# keyboard_controller.net
KiCad netlist of a schematic drawn in Altium Designer
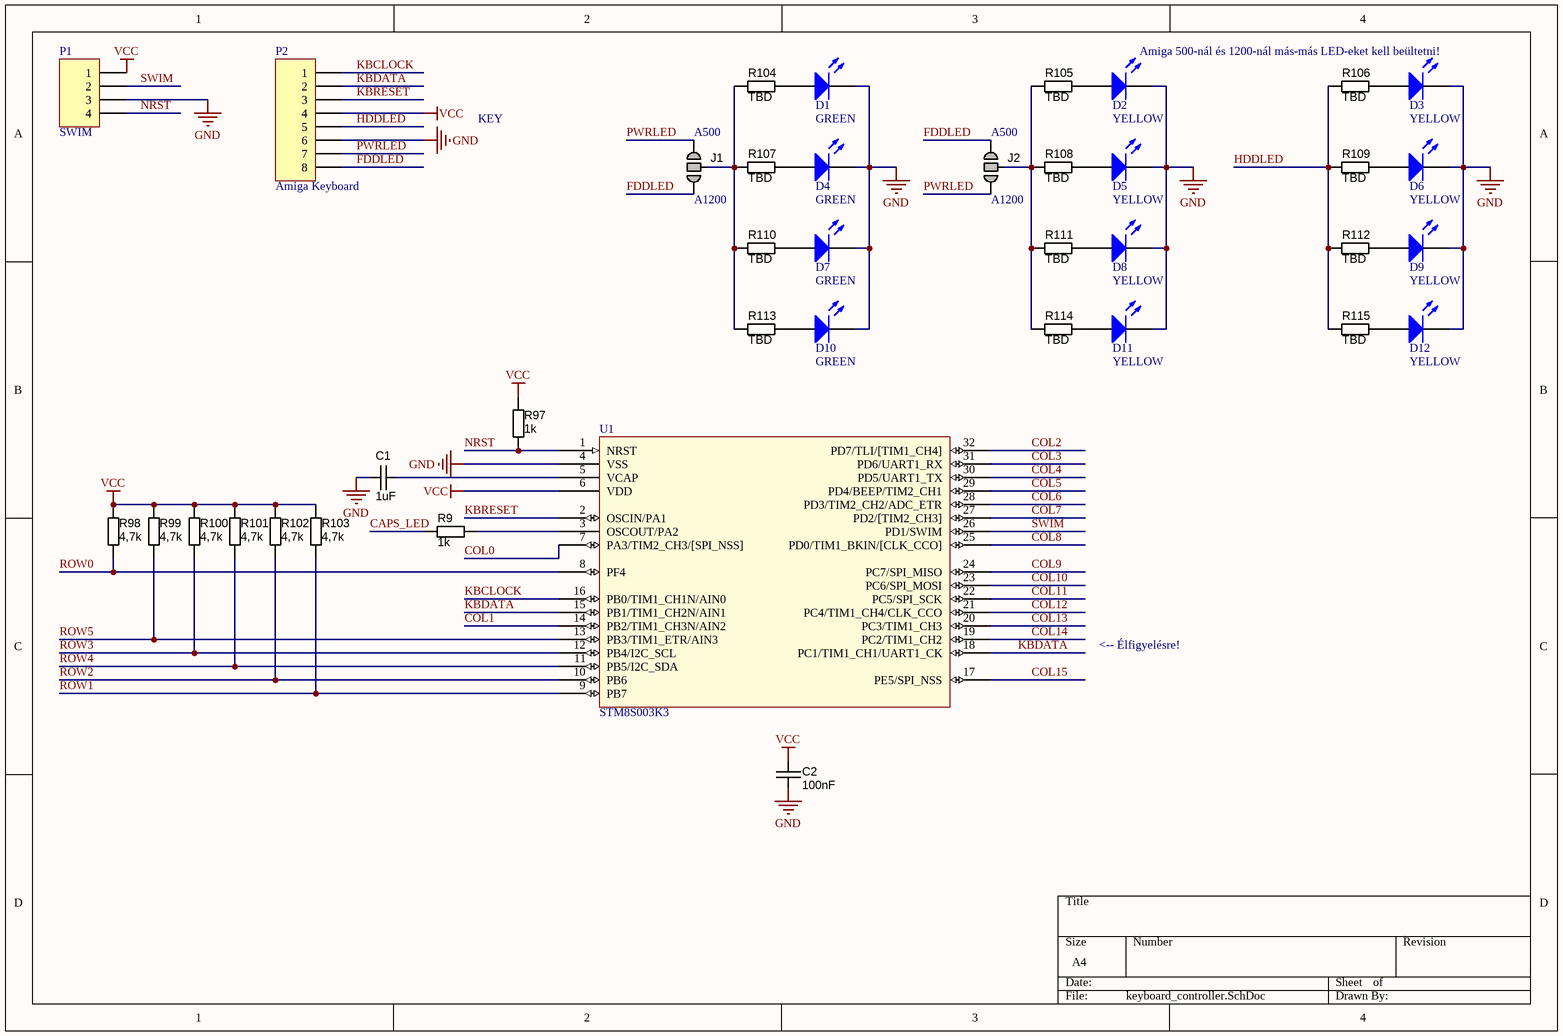
[diagram p0: keyboard_controller.SchDoc]

(export (version "E")
  (design (tool "Eeschema 10.0.6"))
  (components
    (comp (ref "C1")
      (value "1uF")
      (footprint "CAPC2012X135N")
      (description "Capacitor SMD Cer X7R 0805")
      (fields (field (name "TOLERANCE") "±10%") (field (name "Comment") "0805"))
      (libsource (lib "PBL - Capacitors") (part "CAPC_1u_0805_X7R_16V_10%"))
    )
    (comp (ref "C2")
      (value "100nF")
      (footprint "CAPC2012X135N")
      (description "Capacitor SMD Cer X7R 0805")
      (fields (field (name "TOLERANCE") "±10%") (field (name "Comment") "0805"))
      (libsource (lib "PBL - Capacitors") (part "CAPC_1u_0805_X7R_16V_10%"))
    )
    (comp (ref "D1")
      (value "GREEN")
      (footprint "LEDSQ_5mm")
      (description "Typical LED")
      (fields (field (name "PUBLISHER") "Altium Limited"))
      (libsource (lib "keyboard_library") (part "LED"))
    )
    (comp (ref "D2")
      (value "YELLOW")
      (footprint "LEDSQ_5mm")
      (description "Typical LED")
      (fields (field (name "PUBLISHER") "Altium Limited"))
      (libsource (lib "keyboard_library") (part "LED"))
    )
    (comp (ref "D3")
      (value "YELLOW")
      (footprint "LEDSQ_5mm")
      (description "Typical LED")
      (fields (field (name "PUBLISHER") "Altium Limited"))
      (libsource (lib "keyboard_library") (part "LED"))
    )
    (comp (ref "D4")
      (value "GREEN")
      (footprint "LEDSQ_5mm")
      (description "Typical LED")
      (fields (field (name "PUBLISHER") "Altium Limited"))
      (libsource (lib "keyboard_library") (part "LED"))
    )
    (comp (ref "D5")
      (value "YELLOW")
      (footprint "LEDSQ_5mm")
      (description "Typical LED")
      (fields (field (name "PUBLISHER") "Altium Limited"))
      (libsource (lib "keyboard_library") (part "LED"))
    )
    (comp (ref "D6")
      (value "YELLOW")
      (footprint "LEDSQ_5mm")
      (description "Typical LED")
      (fields (field (name "PUBLISHER") "Altium Limited"))
      (libsource (lib "keyboard_library") (part "LED"))
    )
    (comp (ref "D7")
      (value "GREEN")
      (footprint "LEDSQ_5mm")
      (description "Typical LED")
      (fields (field (name "PUBLISHER") "Altium Limited"))
      (libsource (lib "keyboard_library") (part "LED"))
    )
    (comp (ref "D8")
      (value "YELLOW")
      (footprint "LEDSQ_5mm")
      (description "Typical LED")
      (fields (field (name "PUBLISHER") "Altium Limited"))
      (libsource (lib "keyboard_library") (part "LED"))
    )
    (comp (ref "D9")
      (value "YELLOW")
      (footprint "LEDSQ_5mm")
      (description "Typical LED")
      (fields (field (name "PUBLISHER") "Altium Limited"))
      (libsource (lib "keyboard_library") (part "LED"))
    )
    (comp (ref "D10")
      (value "GREEN")
      (footprint "LEDSQ_5mm")
      (description "Typical LED")
      (fields (field (name "PUBLISHER") "Altium Limited"))
      (libsource (lib "keyboard_library") (part "LED"))
    )
    (comp (ref "D11")
      (value "YELLOW")
      (footprint "LEDSQ_5mm")
      (description "Typical LED")
      (fields (field (name "PUBLISHER") "Altium Limited"))
      (libsource (lib "keyboard_library") (part "LED"))
    )
    (comp (ref "D12")
      (value "YELLOW")
      (footprint "LEDSQ_5mm")
      (description "Typical LED")
      (fields (field (name "PUBLISHER") "Altium Limited"))
      (libsource (lib "keyboard_library") (part "LED"))
    )
    (comp (ref "J1")
      (value "Jumper")
      (footprint "Jump_3Way")
      (description "SMD jumper")
      (libsource (lib "PBL - Pads and Jumpers") (part "JUMP_3WAY"))
    )
    (comp (ref "J2")
      (value "Jumper")
      (footprint "Jump_3Way")
      (description "SMD jumper")
      (libsource (lib "PBL - Pads and Jumpers") (part "JUMP_3WAY"))
    )
    (comp (ref "P1")
      (value "SWIM")
      (footprint "HDR1X4")
      (description "Header, 4-Pin")
      (fields (field (name "PUBLISHER") "Altium Limited"))
      (libsource (lib "Miscellaneous Connectors") (part "Header 4"))
    )
    (comp (ref "P2")
      (value "Amiga Keyboard")
      (footprint "HDR1X8")
      (description "Header, 8-Pin")
      (fields (field (name "PUBLISHER") "Altium Limited"))
      (libsource (lib "Miscellaneous Connectors") (part "Header 8"))
    )
    (comp (ref "R9")
      (value "1k")
      (footprint "RESC2012N_ZERO")
      (description "Resistor SMD chip 0.0 Ohm 0.125W 0805")
      (fields (field (name "Comment") "0805"))
      (libsource (lib "") (part "RES_0R_0805_1"))
    )
    (comp (ref "R97")
      (value "1k")
      (footprint "RESC2012N_ZERO")
      (description "Resistor SMD chip 0.0 Ohm 0.125W 0805")
      (fields (field (name "Comment") "0805"))
      (libsource (lib "ZX_Spectrum_library") (part "RES_0R_0805"))
    )
    (comp (ref "R98")
      (value "4,7k")
      (footprint "RESC2012N_ZERO")
      (description "Resistor SMD chip 0.0 Ohm 0.125W 0805")
      (fields (field (name "Comment") "0805"))
      (libsource (lib "ZX_Spectrum_library") (part "RES_0R_0805"))
    )
    (comp (ref "R99")
      (value "4,7k")
      (footprint "RESC2012N_ZERO")
      (description "Resistor SMD chip 0.0 Ohm 0.125W 0805")
      (fields (field (name "Comment") "0805"))
      (libsource (lib "ZX_Spectrum_library") (part "RES_0R_0805"))
    )
    (comp (ref "R100")
      (value "4,7k")
      (footprint "RESC2012N_ZERO")
      (description "Resistor SMD chip 0.0 Ohm 0.125W 0805")
      (fields (field (name "Comment") "0805"))
      (libsource (lib "ZX_Spectrum_library") (part "RES_0R_0805"))
    )
    (comp (ref "R101")
      (value "4,7k")
      (footprint "RESC2012N_ZERO")
      (description "Resistor SMD chip 0.0 Ohm 0.125W 0805")
      (fields (field (name "Comment") "0805"))
      (libsource (lib "ZX_Spectrum_library") (part "RES_0R_0805"))
    )
    (comp (ref "R102")
      (value "4,7k")
      (footprint "RESC2012N_ZERO")
      (description "Resistor SMD chip 0.0 Ohm 0.125W 0805")
      (fields (field (name "Comment") "0805"))
      (libsource (lib "ZX_Spectrum_library") (part "RES_0R_0805"))
    )
    (comp (ref "R103")
      (value "4,7k")
      (footprint "RESC2012N_ZERO")
      (description "Resistor SMD chip 0.0 Ohm 0.125W 0805")
      (fields (field (name "Comment") "0805"))
      (libsource (lib "ZX_Spectrum_library") (part "RES_0R_0805"))
    )
    (comp (ref "R104")
      (value "TBD")
      (footprint "RESC2012N_ZERO")
      (description "Resistor SMD chip 0.0 Ohm 0.125W 0805")
      (fields (field (name "Comment") "0805"))
      (libsource (lib "") (part "RES_0R_0805_1"))
    )
    (comp (ref "R105")
      (value "TBD")
      (footprint "RESC2012N_ZERO")
      (description "Resistor SMD chip 0.0 Ohm 0.125W 0805")
      (fields (field (name "Comment") "0805"))
      (libsource (lib "") (part "RES_0R_0805_1"))
    )
    (comp (ref "R106")
      (value "TBD")
      (footprint "RESC2012N_ZERO")
      (description "Resistor SMD chip 0.0 Ohm 0.125W 0805")
      (fields (field (name "Comment") "0805"))
      (libsource (lib "") (part "RES_0R_0805_1"))
    )
    (comp (ref "R107")
      (value "TBD")
      (footprint "RESC2012N_ZERO")
      (description "Resistor SMD chip 0.0 Ohm 0.125W 0805")
      (fields (field (name "Comment") "0805"))
      (libsource (lib "") (part "RES_0R_0805_1"))
    )
    (comp (ref "R108")
      (value "TBD")
      (footprint "RESC2012N_ZERO")
      (description "Resistor SMD chip 0.0 Ohm 0.125W 0805")
      (fields (field (name "Comment") "0805"))
      (libsource (lib "") (part "RES_0R_0805_1"))
    )
    (comp (ref "R109")
      (value "TBD")
      (footprint "RESC2012N_ZERO")
      (description "Resistor SMD chip 0.0 Ohm 0.125W 0805")
      (fields (field (name "Comment") "0805"))
      (libsource (lib "") (part "RES_0R_0805_1"))
    )
    (comp (ref "R110")
      (value "TBD")
      (footprint "RESC2012N_ZERO")
      (description "Resistor SMD chip 0.0 Ohm 0.125W 0805")
      (fields (field (name "Comment") "0805"))
      (libsource (lib "") (part "RES_0R_0805_1"))
    )
    (comp (ref "R111")
      (value "TBD")
      (footprint "RESC2012N_ZERO")
      (description "Resistor SMD chip 0.0 Ohm 0.125W 0805")
      (fields (field (name "Comment") "0805"))
      (libsource (lib "") (part "RES_0R_0805_1"))
    )
    (comp (ref "R112")
      (value "TBD")
      (footprint "RESC2012N_ZERO")
      (description "Resistor SMD chip 0.0 Ohm 0.125W 0805")
      (fields (field (name "Comment") "0805"))
      (libsource (lib "") (part "RES_0R_0805_1"))
    )
    (comp (ref "R113")
      (value "TBD")
      (footprint "RESC2012N_ZERO")
      (description "Resistor SMD chip 0.0 Ohm 0.125W 0805")
      (fields (field (name "Comment") "0805"))
      (libsource (lib "") (part "RES_0R_0805_1"))
    )
    (comp (ref "R114")
      (value "TBD")
      (footprint "RESC2012N_ZERO")
      (description "Resistor SMD chip 0.0 Ohm 0.125W 0805")
      (fields (field (name "Comment") "0805"))
      (libsource (lib "") (part "RES_0R_0805_1"))
    )
    (comp (ref "R115")
      (value "TBD")
      (footprint "RESC2012N_ZERO")
      (description "Resistor SMD chip 0.0 Ohm 0.125W 0805")
      (fields (field (name "Comment") "0805"))
      (libsource (lib "") (part "RES_0R_0805_1"))
    )
    (comp (ref "U1")
      (value "STM8S003K3")
      (footprint "LQFP32_M")
      (description "ST Microelectronics STM8S003K3 microcontroller")
      (libsource (lib "keyboard_library") (part "STM8S003K3"))
    )
  )
  (nets
    (net (code "1") (name "/CAPS_LED") (class "Default")
      (node (ref "R9") (pin "1") (pinfunction "1_1") (pintype "passive"))
    )
    (net (code "2") (name "/COL0") (class "Default")
      (node (ref "U1") (pin "7") (pinfunction "PA3/TIM2_CH3/[SPI_NSS]_7") (pintype "bidirectional"))
    )
    (net (code "3") (name "/COL1") (class "Default")
      (node (ref "U1") (pin "14") (pinfunction "PB2/TIM1_CH3N/AIN2_14") (pintype "bidirectional"))
    )
    (net (code "4") (name "/COL2") (class "Default")
      (node (ref "U1") (pin "32") (pinfunction "PD7/TLI/[TIM1_CH4]_32") (pintype "bidirectional"))
    )
    (net (code "5") (name "/COL3") (class "Default")
      (node (ref "U1") (pin "31") (pinfunction "PD6/UART1_RX_31") (pintype "bidirectional"))
    )
    (net (code "6") (name "/COL4") (class "Default")
      (node (ref "U1") (pin "30") (pinfunction "PD5/UART1_TX_30") (pintype "bidirectional"))
    )
    (net (code "7") (name "/COL5") (class "Default")
      (node (ref "U1") (pin "29") (pinfunction "PD4/BEEP/TIM2_CH1_29") (pintype "bidirectional"))
    )
    (net (code "8") (name "/COL6") (class "Default")
      (node (ref "U1") (pin "28") (pinfunction "PD3/TIM2_CH2/ADC_ETR_28") (pintype "bidirectional"))
    )
    (net (code "9") (name "/COL7") (class "Default")
      (node (ref "U1") (pin "27") (pinfunction "PD2/[TIM2_CH3]_27") (pintype "bidirectional"))
    )
    (net (code "10") (name "/COL8") (class "Default")
      (node (ref "U1") (pin "25") (pinfunction "PD0/TIM1_BKIN/[CLK_CCO]_25") (pintype "bidirectional"))
    )
    (net (code "11") (name "/COL9") (class "Default")
      (node (ref "U1") (pin "24") (pinfunction "PC7/SPI_MISO_24") (pintype "bidirectional"))
    )
    (net (code "12") (name "/COL10") (class "Default")
      (node (ref "U1") (pin "23") (pinfunction "PC6/SPI_MOSI_23") (pintype "bidirectional"))
    )
    (net (code "13") (name "/COL11") (class "Default")
      (node (ref "U1") (pin "22") (pinfunction "PC5/SPI_SCK_22") (pintype "bidirectional"))
    )
    (net (code "14") (name "/COL12") (class "Default")
      (node (ref "U1") (pin "21") (pinfunction "PC4/TIM1_CH4/CLK_CCO_21") (pintype "bidirectional"))
    )
    (net (code "15") (name "/COL13") (class "Default")
      (node (ref "U1") (pin "20") (pinfunction "PC3/TIM1_CH3_20") (pintype "bidirectional"))
    )
    (net (code "16") (name "/COL14") (class "Default")
      (node (ref "U1") (pin "19") (pinfunction "PC2/TIM1_CH2_19") (pintype "bidirectional"))
    )
    (net (code "17") (name "/COL15") (class "Default")
      (node (ref "U1") (pin "17") (pinfunction "PE5/SPI_NSS_17") (pintype "bidirectional"))
    )
    (net (code "18") (name "/FDDLED") (class "Default")
      (node (ref "J1") (pin "1") (pinfunction "1_1") (pintype "passive"))
      (node (ref "J2") (pin "3") (pinfunction "3_3") (pintype "passive"))
      (node (ref "P2") (pin "8") (pinfunction "8_8") (pintype "passive"))
    )
    (net (code "19") (name "/HDDLED") (class "Default")
      (node (ref "P2") (pin "5") (pinfunction "5_5") (pintype "passive"))
      (node (ref "R106") (pin "1") (pinfunction "1_1") (pintype "passive"))
      (node (ref "R109") (pin "1") (pinfunction "1_1") (pintype "passive"))
      (node (ref "R112") (pin "1") (pinfunction "1_1") (pintype "passive"))
      (node (ref "R115") (pin "1") (pinfunction "1_1") (pintype "passive"))
    )
    (net (code "20") (name "/KBCLOCK") (class "Default")
      (node (ref "P2") (pin "1") (pinfunction "1_1") (pintype "passive"))
      (node (ref "U1") (pin "16") (pinfunction "PB0/TIM1_CH1N/AIN0_16") (pintype "bidirectional"))
    )
    (net (code "21") (name "/KBDATA") (class "Default")
      (node (ref "P2") (pin "2") (pinfunction "2_2") (pintype "passive"))
      (node (ref "U1") (pin "15") (pinfunction "PB1/TIM1_CH2N/AIN1_15") (pintype "bidirectional"))
      (node (ref "U1") (pin "18") (pinfunction "PC1/TIM1_CH1/UART1_CK_18") (pintype "bidirectional"))
    )
    (net (code "22") (name "/KBRESET") (class "Default")
      (node (ref "P2") (pin "3") (pinfunction "3_3") (pintype "passive"))
      (node (ref "U1") (pin "2") (pinfunction "OSCIN/PA1_2") (pintype "bidirectional"))
    )
    (net (code "23") (name "/NRST") (class "Default")
      (node (ref "P1") (pin "4") (pinfunction "4_4") (pintype "passive"))
      (node (ref "R97") (pin "1") (pinfunction "1_1") (pintype "passive"))
      (node (ref "U1") (pin "1") (pinfunction "NRST_1") (pintype "input"))
    )
    (net (code "24") (name "/PWRLED") (class "Default")
      (node (ref "J1") (pin "3") (pinfunction "3_3") (pintype "passive"))
      (node (ref "J2") (pin "1") (pinfunction "1_1") (pintype "passive"))
      (node (ref "P2") (pin "7") (pinfunction "7_7") (pintype "passive"))
    )
    (net (code "25") (name "/ROW0") (class "Default")
      (node (ref "R98") (pin "1") (pinfunction "1_1") (pintype "passive"))
      (node (ref "U1") (pin "8") (pinfunction "PF4_8") (pintype "bidirectional"))
    )
    (net (code "26") (name "/ROW1") (class "Default")
      (node (ref "R103") (pin "1") (pinfunction "1_1") (pintype "passive"))
      (node (ref "U1") (pin "9") (pinfunction "PB7_9") (pintype "bidirectional"))
    )
    (net (code "27") (name "/ROW2") (class "Default")
      (node (ref "R102") (pin "1") (pinfunction "1_1") (pintype "passive"))
      (node (ref "U1") (pin "10") (pinfunction "PB6_10") (pintype "bidirectional"))
    )
    (net (code "28") (name "/ROW3") (class "Default")
      (node (ref "R100") (pin "1") (pinfunction "1_1") (pintype "passive"))
      (node (ref "U1") (pin "12") (pinfunction "PB4/I2C_SCL_12") (pintype "bidirectional"))
    )
    (net (code "29") (name "/ROW4") (class "Default")
      (node (ref "R101") (pin "1") (pinfunction "1_1") (pintype "passive"))
      (node (ref "U1") (pin "11") (pinfunction "PB5/I2C_SDA_11") (pintype "bidirectional"))
    )
    (net (code "30") (name "/ROW5") (class "Default")
      (node (ref "R99") (pin "1") (pinfunction "1_1") (pintype "passive"))
      (node (ref "U1") (pin "13") (pinfunction "PB3/TIM1_ETR/AIN3_13") (pintype "bidirectional"))
    )
    (net (code "31") (name "/SWIM") (class "Default")
      (node (ref "P1") (pin "2") (pinfunction "2_2") (pintype "passive"))
      (node (ref "U1") (pin "26") (pinfunction "PD1/SWIM_26") (pintype "bidirectional"))
    )
    (net (code "32") (name "GND") (class "Default")
      (node (ref "C1") (pin "2") (pintype "passive"))
      (node (ref "C2") (pin "2") (pintype "passive"))
      (node (ref "D1") (pin "2") (pinfunction "K_2") (pintype "passive"))
      (node (ref "D10") (pin "2") (pinfunction "K_2") (pintype "passive"))
      (node (ref "D11") (pin "2") (pinfunction "K_2") (pintype "passive"))
      (node (ref "D12") (pin "2") (pinfunction "K_2") (pintype "passive"))
      (node (ref "D2") (pin "2") (pinfunction "K_2") (pintype "passive"))
      (node (ref "D3") (pin "2") (pinfunction "K_2") (pintype "passive"))
      (node (ref "D4") (pin "2") (pinfunction "K_2") (pintype "passive"))
      (node (ref "D5") (pin "2") (pinfunction "K_2") (pintype "passive"))
      (node (ref "D6") (pin "2") (pinfunction "K_2") (pintype "passive"))
      (node (ref "D7") (pin "2") (pinfunction "K_2") (pintype "passive"))
      (node (ref "D8") (pin "2") (pinfunction "K_2") (pintype "passive"))
      (node (ref "D9") (pin "2") (pinfunction "K_2") (pintype "passive"))
      (node (ref "P1") (pin "3") (pinfunction "3_3") (pintype "passive"))
      (node (ref "P2") (pin "6") (pinfunction "6_6") (pintype "passive"))
      (node (ref "U1") (pin "4") (pinfunction "VSS_4") (pintype "power_in"))
    )
    (net (code "33") (name "Net-(D1-A)") (class "Default")
      (node (ref "D1") (pin "1") (pinfunction "A_1") (pintype "passive"))
      (node (ref "R104") (pin "2") (pinfunction "2_2") (pintype "passive"))
    )
    (net (code "34") (name "Net-(D2-A)") (class "Default")
      (node (ref "D2") (pin "1") (pinfunction "A_1") (pintype "passive"))
      (node (ref "R105") (pin "2") (pinfunction "2_2") (pintype "passive"))
    )
    (net (code "35") (name "Net-(D3-A)") (class "Default")
      (node (ref "D3") (pin "1") (pinfunction "A_1") (pintype "passive"))
      (node (ref "R106") (pin "2") (pinfunction "2_2") (pintype "passive"))
    )
    (net (code "36") (name "Net-(D4-A)") (class "Default")
      (node (ref "D4") (pin "1") (pinfunction "A_1") (pintype "passive"))
      (node (ref "R107") (pin "2") (pinfunction "2_2") (pintype "passive"))
    )
    (net (code "37") (name "Net-(D5-A)") (class "Default")
      (node (ref "D5") (pin "1") (pinfunction "A_1") (pintype "passive"))
      (node (ref "R108") (pin "2") (pinfunction "2_2") (pintype "passive"))
    )
    (net (code "38") (name "Net-(D6-A)") (class "Default")
      (node (ref "D6") (pin "1") (pinfunction "A_1") (pintype "passive"))
      (node (ref "R109") (pin "2") (pinfunction "2_2") (pintype "passive"))
    )
    (net (code "39") (name "Net-(D7-A)") (class "Default")
      (node (ref "D7") (pin "1") (pinfunction "A_1") (pintype "passive"))
      (node (ref "R110") (pin "2") (pinfunction "2_2") (pintype "passive"))
    )
    (net (code "40") (name "Net-(D8-A)") (class "Default")
      (node (ref "D8") (pin "1") (pinfunction "A_1") (pintype "passive"))
      (node (ref "R111") (pin "2") (pinfunction "2_2") (pintype "passive"))
    )
    (net (code "41") (name "Net-(D9-A)") (class "Default")
      (node (ref "D9") (pin "1") (pinfunction "A_1") (pintype "passive"))
      (node (ref "R112") (pin "2") (pinfunction "2_2") (pintype "passive"))
    )
    (net (code "42") (name "Net-(D10-A)") (class "Default")
      (node (ref "D10") (pin "1") (pinfunction "A_1") (pintype "passive"))
      (node (ref "R113") (pin "2") (pinfunction "2_2") (pintype "passive"))
    )
    (net (code "43") (name "Net-(D11-A)") (class "Default")
      (node (ref "D11") (pin "1") (pinfunction "A_1") (pintype "passive"))
      (node (ref "R114") (pin "2") (pinfunction "2_2") (pintype "passive"))
    )
    (net (code "44") (name "Net-(D12-A)") (class "Default")
      (node (ref "D12") (pin "1") (pinfunction "A_1") (pintype "passive"))
      (node (ref "R115") (pin "2") (pinfunction "2_2") (pintype "passive"))
    )
    (net (code "45") (name "Net-(J1-Pad2)") (class "Default")
      (node (ref "J1") (pin "2") (pinfunction "2_2") (pintype "passive"))
      (node (ref "R104") (pin "1") (pinfunction "1_1") (pintype "passive"))
      (node (ref "R107") (pin "1") (pinfunction "1_1") (pintype "passive"))
      (node (ref "R110") (pin "1") (pinfunction "1_1") (pintype "passive"))
      (node (ref "R113") (pin "1") (pinfunction "1_1") (pintype "passive"))
    )
    (net (code "46") (name "Net-(J2-Pad2)") (class "Default")
      (node (ref "J2") (pin "2") (pinfunction "2_2") (pintype "passive"))
      (node (ref "R105") (pin "1") (pinfunction "1_1") (pintype "passive"))
      (node (ref "R108") (pin "1") (pinfunction "1_1") (pintype "passive"))
      (node (ref "R111") (pin "1") (pinfunction "1_1") (pintype "passive"))
      (node (ref "R114") (pin "1") (pinfunction "1_1") (pintype "passive"))
    )
    (net (code "47") (name "Net-(U1-OSCOUT{slash}PA2)") (class "Default")
      (node (ref "R9") (pin "2") (pinfunction "2_2") (pintype "passive"))
      (node (ref "U1") (pin "3") (pinfunction "OSCOUT/PA2_3") (pintype "passive"))
    )
    (net (code "48") (name "Net-(U1-VCAP)") (class "Default")
      (node (ref "C1") (pin "1") (pintype "passive"))
      (node (ref "U1") (pin "5") (pinfunction "VCAP_5") (pintype "passive"))
    )
    (net (code "49") (name "VCC") (class "Default")
      (node (ref "C2") (pin "1") (pintype "passive"))
      (node (ref "P1") (pin "1") (pinfunction "1_1") (pintype "passive"))
      (node (ref "P2") (pin "4") (pinfunction "4_4") (pintype "passive"))
      (node (ref "R100") (pin "2") (pinfunction "2_2") (pintype "passive"))
      (node (ref "R101") (pin "2") (pinfunction "2_2") (pintype "passive"))
      (node (ref "R102") (pin "2") (pinfunction "2_2") (pintype "passive"))
      (node (ref "R103") (pin "2") (pinfunction "2_2") (pintype "passive"))
      (node (ref "R97") (pin "2") (pinfunction "2_2") (pintype "passive"))
      (node (ref "R98") (pin "2") (pinfunction "2_2") (pintype "passive"))
      (node (ref "R99") (pin "2") (pinfunction "2_2") (pintype "passive"))
      (node (ref "U1") (pin "6") (pinfunction "VDD_6") (pintype "power_in"))
    )
  )
)
